# LPCB220_-_THROTTLE_ISO_CHANNEL.net
KiCad netlist of a schematic drawn in Altium Designer
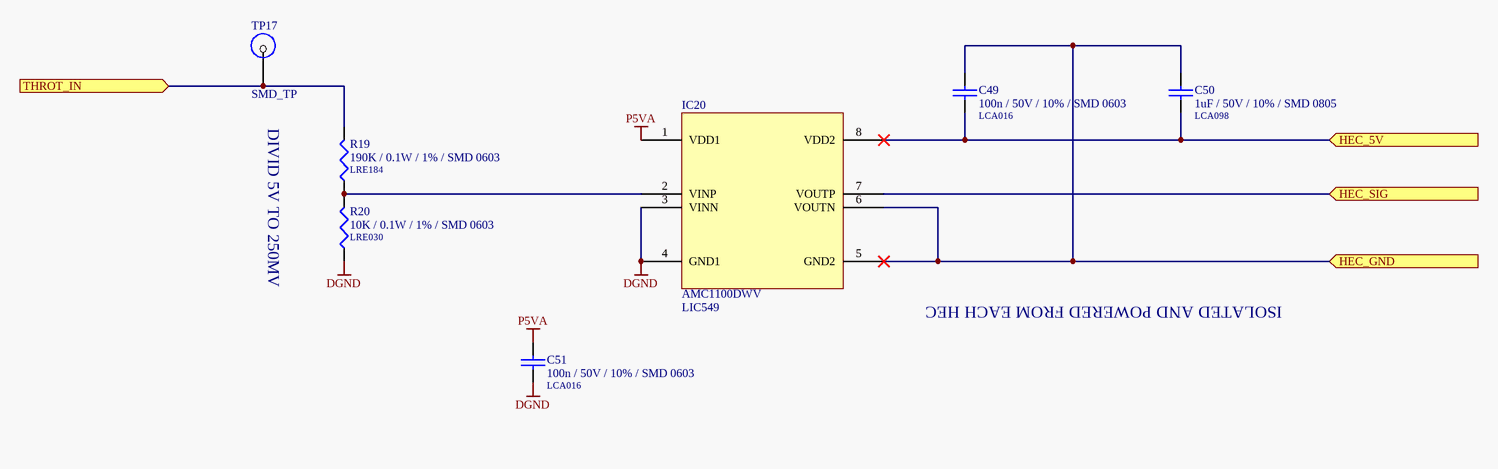
[diagram p0: LPCB220 - THROTTLE ISO CHANNEL.SchDoc]

(export (version "E")
  (design (tool "Eeschema 10.0.6"))
  (components
    (comp (ref "C49")
      (value "100n / 50V / 10% / SMD 0603")
      (footprint "LFP011__CC1608-0603-IPC7351_B")
      (description "Capacitor, Ceramic Chip, 100nF (0.1uF), 50V, 5%, SMD 0603 [LCA016]")
      (fields (field (name "LDL_NUMBER") "LCA016"))
      (libsource (lib "LDL_Capacitors") (part "100n / 50V / 10% / SMD 0603"))
    )
    (comp (ref "C50")
      (value "1uF / 50V / 10% / SMD 0805")
      (footprint "LFP010__CC2012-0805-IPC7351_B")
      (description "Capacitor, Ceramic Chip, 1uF, 50V, SMD 0805 [LCA098]")
      (fields (field (name "LDL_NUMBER") "LCA098"))
      (libsource (lib "LDL_Capacitors") (part "1uF / 50V / 10% / SMD 0805"))
    )
    (comp (ref "C51")
      (value "100n / 50V / 10% / SMD 0603")
      (footprint "LFP011__CC1608-0603-IPC7351_B")
      (description "Capacitor, Ceramic Chip, 100nF (0.1uF), 50V, 5%, SMD 0603 [LCA016]")
      (fields (field (name "LDL_NUMBER") "LCA016"))
      (libsource (lib "LDL_Capacitors") (part "100n / 50V / 10% / SMD 0603"))
    )
    (comp (ref "IC20")
      (value "AMC1100DWV")
      (footprint "LFP116__R-PDSO-G8")
      (description "IC, Isolation Amplifier, SMD SOIC8 [LIC549]")
      (fields (field (name "LDL_NUMBER") "LIC549"))
      (libsource (lib "LDL_Semiconductors") (part "AMC1100DWV"))
    )
    (comp (ref "R19")
      (value "190K / 0.1W / 1% / SMD 0603")
      (footprint "LFP020__CR1608-0603-IPC7351_B")
      (description "Resistor, Ceramic Chip, 190K, 0.1W, 1%, SMD 0603 [LRE184]")
      (fields (field (name "LDL_NUMBER") "LRE184"))
      (libsource (lib "LDL_Resistors") (part "190K / 0.1W / 1% / SMD 0603"))
    )
    (comp (ref "R20")
      (value "10K / 0.1W / 1% / SMD 0603")
      (footprint "LFP020__CR1608-0603-IPC7351_B")
      (description "Resistor, Ceramic Chip, 10K, 0.1W, 1%, SMD 0603 [LRE030]")
      (fields (field (name "LDL_NUMBER") "LRE030"))
      (libsource (lib "LDL_Resistors") (part "10K / 0.1W / 1% / SMD 0603"))
    )
    (comp (ref "TP17")
      (value "SMD_TP")
      (footprint "SMD-TP")
      (description "SMD Test Point")
      (libsource (lib "LDL_Connectors") (part "SMD_TP"))
    )
  )
  (nets
    (net (code "1") (name "/HEC_5V") (class "Default")
      (node (ref "C49") (pin "2") (pintype "passive"))
      (node (ref "C50") (pin "2") (pintype "passive"))
      (node (ref "IC20") (pin "8") (pinfunction "VDD2_8") (pintype "power_in"))
    )
    (net (code "2") (name "/HEC_GND") (class "Default")
      (node (ref "C49") (pin "1") (pintype "passive"))
      (node (ref "C50") (pin "1") (pintype "passive"))
      (node (ref "IC20") (pin "5") (pinfunction "GND2_5") (pintype "power_in"))
      (node (ref "IC20") (pin "6") (pinfunction "VOUTN_6") (pintype "passive"))
    )
    (net (code "3") (name "/HEC_SIG") (class "Default")
      (node (ref "IC20") (pin "7") (pinfunction "VOUTP_7") (pintype "passive"))
    )
    (net (code "4") (name "/THROT_IN") (class "Default")
      (node (ref "R19") (pin "2") (pintype "passive"))
      (node (ref "TP17") (pin "1") (pintype "passive"))
    )
    (net (code "5") (name "DGND") (class "Default")
      (node (ref "C51") (pin "2") (pintype "passive"))
      (node (ref "IC20") (pin "3") (pinfunction "VINN_3") (pintype "passive"))
      (node (ref "IC20") (pin "4") (pinfunction "GND1_4") (pintype "power_in"))
      (node (ref "R20") (pin "1") (pintype "passive"))
    )
    (net (code "6") (name "Net-(IC20-VINP)") (class "Default")
      (node (ref "IC20") (pin "2") (pinfunction "VINP_2") (pintype "passive"))
      (node (ref "R19") (pin "1") (pintype "passive"))
      (node (ref "R20") (pin "2") (pintype "passive"))
    )
    (net (code "7") (name "P5VA") (class "Default")
      (node (ref "C51") (pin "1") (pintype "passive"))
      (node (ref "IC20") (pin "1") (pinfunction "VDD1_1") (pintype "power_in"))
    )
  )
)
